# T-11_Version_1_2.net
KiCad netlist of a schematic drawn in EAGLE
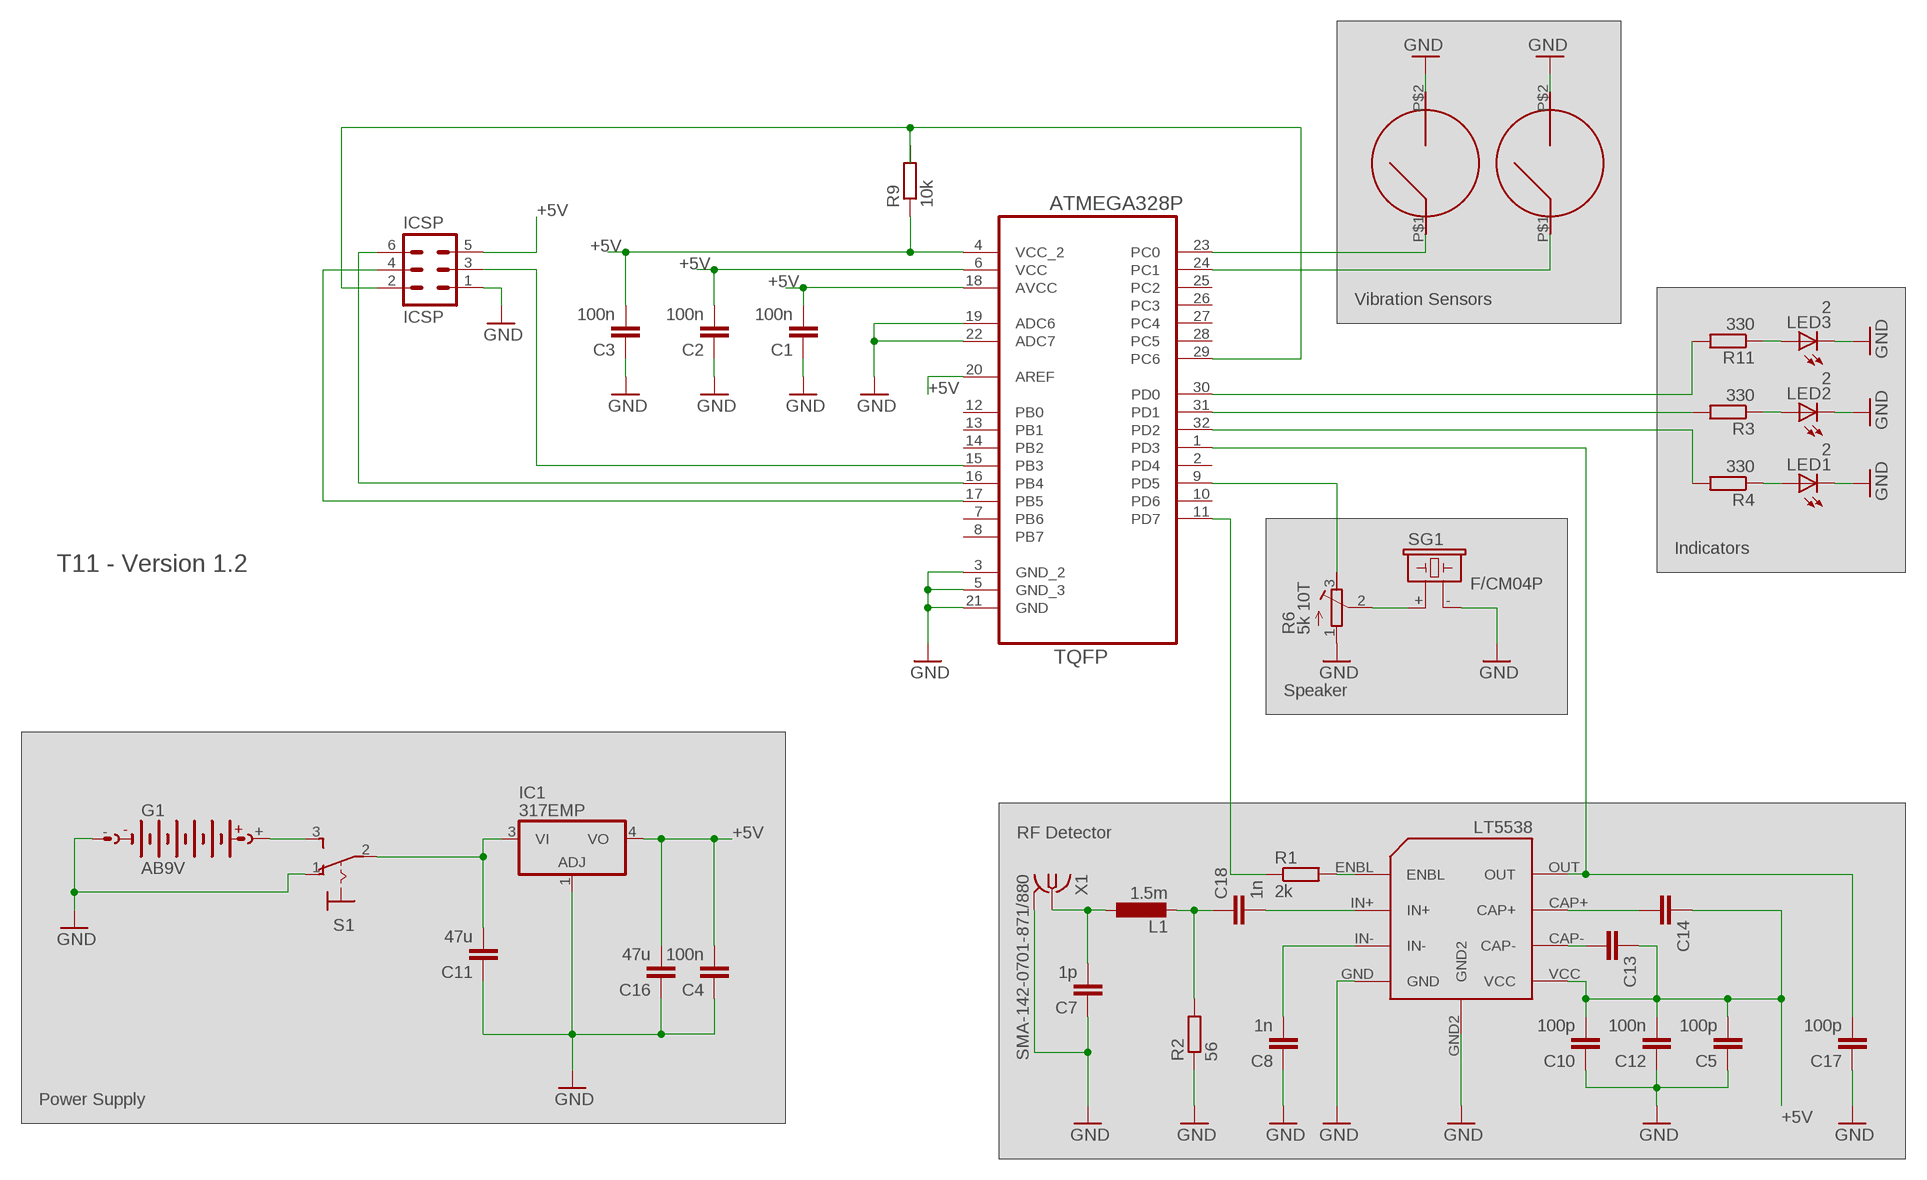
[diagram p0: schematic, sheet 1]

(export (version "E")
  (design (tool "Eeschema 10.0.6"))
  (components
    (comp (ref "C1")
      (value "100n")
      (footprint "eagle-import:C4532")
      (libsource (lib "eagle-import") (part "C-EUC4532"))
    )
    (comp (ref "C2")
      (value "100n")
      (footprint "eagle-import:C4532")
      (libsource (lib "eagle-import") (part "C-EUC4532"))
    )
    (comp (ref "C3")
      (value "100n")
      (footprint "eagle-import:C4532")
      (libsource (lib "eagle-import") (part "C-EUC4532"))
    )
    (comp (ref "C4")
      (value "100n")
      (footprint "eagle-import:C4532")
      (libsource (lib "eagle-import") (part "C-EUC4532"))
    )
    (comp (ref "C5")
      (value "100p")
      (footprint "eagle-import:C4532")
      (libsource (lib "eagle-import") (part "C-EUC4532"))
    )
    (comp (ref "C7")
      (value "1p")
      (footprint "eagle-import:C4532")
      (libsource (lib "eagle-import") (part "C-EUC4532"))
    )
    (comp (ref "C8")
      (value "1n")
      (footprint "eagle-import:C4532")
      (libsource (lib "eagle-import") (part "C-EUC4532"))
    )
    (comp (ref "C10")
      (value "100p")
      (footprint "eagle-import:C4532")
      (libsource (lib "eagle-import") (part "C-EUC4532"))
    )
    (comp (ref "C11")
      (value "47u")
      (footprint "eagle-import:C4532")
      (libsource (lib "eagle-import") (part "C-EUC4532"))
    )
    (comp (ref "C12")
      (value "100n")
      (footprint "eagle-import:C4532")
      (libsource (lib "eagle-import") (part "C-EUC4532"))
    )
    (comp (ref "C13")
      (value "C-EUC4532")
      (footprint "eagle-import:C4532")
      (libsource (lib "eagle-import") (part "C-EUC4532"))
    )
    (comp (ref "C14")
      (value "C-EUC4532")
      (footprint "eagle-import:C4532")
      (libsource (lib "eagle-import") (part "C-EUC4532"))
    )
    (comp (ref "C16")
      (value "47u")
      (footprint "eagle-import:C4532")
      (libsource (lib "eagle-import") (part "C-EUC4532"))
    )
    (comp (ref "C17")
      (value "100p")
      (footprint "eagle-import:C4532")
      (libsource (lib "eagle-import") (part "C-EUC4532"))
    )
    (comp (ref "C18")
      (value "1n")
      (footprint "eagle-import:C4532")
      (libsource (lib "eagle-import") (part "C-EUC4532"))
    )
    (comp (ref "G1")
      (value "AB9V")
      (footprint "eagle-import:AB9V")
      (libsource (lib "eagle-import") (part "AB9V"))
    )
    (comp (ref "IC1")
      (value "317EMP")
      (footprint "eagle-import:SOT223")
      (libsource (lib "eagle-import") (part "317EMP"))
    )
    (comp (ref "ICSP")
      (value "ICSP")
      (footprint "eagle-import:MA03-2")
      (libsource (lib "eagle-import") (part "MA03-2"))
    )
    (comp (ref "L1")
      (value "1.5m")
      (footprint "eagle-import:L4532P")
      (libsource (lib "eagle-import") (part "L-EUL4532P"))
    )
    (comp (ref "LED1")
      (value "2")
      (footprint "eagle-import:LED3MM")
      (libsource (lib "eagle-import") (part "LED3MM"))
    )
    (comp (ref "LED2")
      (value "2")
      (footprint "eagle-import:LED3MM")
      (libsource (lib "eagle-import") (part "LED3MM"))
    )
    (comp (ref "LED3")
      (value "2")
      (footprint "eagle-import:LED3MM")
      (libsource (lib "eagle-import") (part "LED3MM"))
    )
    (comp (ref "R1")
      (value "2k")
      (footprint "eagle-import:R3225")
      (libsource (lib "eagle-import") (part "R-EU_R3225"))
    )
    (comp (ref "R2")
      (value "56")
      (footprint "eagle-import:R3225")
      (libsource (lib "eagle-import") (part "R-EU_R3225"))
    )
    (comp (ref "R3")
      (value "330")
      (footprint "eagle-import:R3225")
      (libsource (lib "eagle-import") (part "R-EU_R3225"))
    )
    (comp (ref "R4")
      (value "330")
      (footprint "eagle-import:R3225")
      (libsource (lib "eagle-import") (part "R-EU_R3225"))
    )
    (comp (ref "R6")
      (value "5k 10T")
      (footprint "eagle-import:RTRIMTS63Y")
      (libsource (lib "eagle-import") (part "R-TRIMMTS63Y"))
    )
    (comp (ref "R9")
      (value "10k")
      (footprint "eagle-import:R3225")
      (libsource (lib "eagle-import") (part "R-EU_R3225"))
    )
    (comp (ref "R11")
      (value "330")
      (footprint "eagle-import:R3225")
      (libsource (lib "eagle-import") (part "R-EU_R3225"))
    )
    (comp (ref "S1")
      (value "320-916")
      (footprint "eagle-import:320-916")
      (libsource (lib "eagle-import") (part "320-916"))
    )
    (comp (ref "SG1")
      (value "F/CM04P")
      (footprint "eagle-import:F_CM04P")
      (libsource (lib "eagle-import") (part "F/CM04P"))
    )
    (comp (ref "U$1")
      (value "LT5538")
      (footprint "eagle-import:LT5538")
      (libsource (lib "eagle-import") (part "LT5538"))
    )
    (comp (ref "U$2")
      (value "SW-1801X")
      (footprint "eagle-import:SW-1801X")
      (libsource (lib "eagle-import") (part "SW-1801X"))
    )
    (comp (ref "U$3")
      (value "SW-1801X")
      (footprint "eagle-import:SW-1801X")
      (libsource (lib "eagle-import") (part "SW-1801X"))
    )
    (comp (ref "U1")
      (value "ATMEGA328P-AU")
      (footprint "eagle-import:QFP80P900X900X120-32N")
      (libsource (lib "eagle-import") (part "ATMEGA328P-AU"))
    )
    (comp (ref "X1")
      (value "SMA-142-0701-871/880")
      (footprint "eagle-import:SMA-142-0701-871")
      (fields (field (name "MF") "JOHNSON COMPONENTS") (field (name "MPN") "142-0701-871"))
      (libsource (lib "eagle-import") (part "SMA-142-0701-871/880"))
    )
  )
  (nets
    (net (code "1") (name "/+5V") (class "Default")
      (node (ref "C1") (pin "2") (pinfunction "2_2") (pintype "passive"))
      (node (ref "C10") (pin "2") (pinfunction "2_2") (pintype "passive"))
      (node (ref "C12") (pin "2") (pinfunction "2_2") (pintype "passive"))
      (node (ref "C13") (pin "1") (pinfunction "1_1") (pintype "passive"))
      (node (ref "C14") (pin "1") (pinfunction "1_1") (pintype "passive"))
      (node (ref "C16") (pin "2") (pinfunction "2_2") (pintype "passive"))
      (node (ref "C2") (pin "2") (pinfunction "2_2") (pintype "passive"))
      (node (ref "C3") (pin "2") (pinfunction "2_2") (pintype "passive"))
      (node (ref "C4") (pin "2") (pinfunction "2_2") (pintype "passive"))
      (node (ref "C5") (pin "2") (pinfunction "2_2") (pintype "passive"))
      (node (ref "IC1") (pin "4") (pinfunction "VO_4") (pintype "passive"))
      (node (ref "ICSP") (pin "5") (pinfunction "5_5") (pintype "passive"))
      (node (ref "R9") (pin "1") (pinfunction "1_1") (pintype "passive"))
      (node (ref "U$1") (pin "VCC") (pinfunction "VCC_VCC") (pintype "power_in"))
      (node (ref "U1") (pin "18") (pinfunction "AVCC_18") (pintype "power_in"))
      (node (ref "U1") (pin "20") (pinfunction "AREF_20") (pintype "input"))
      (node (ref "U1") (pin "4") (pinfunction "VCC_2_4") (pintype "power_in"))
      (node (ref "U1") (pin "6") (pinfunction "VCC_6") (pintype "power_in"))
    )
    (net (code "2") (name "GND") (class "Default")
      (node (ref "C1") (pin "1") (pinfunction "1_1") (pintype "passive"))
      (node (ref "C10") (pin "1") (pinfunction "1_1") (pintype "passive"))
      (node (ref "C11") (pin "1") (pinfunction "1_1") (pintype "passive"))
      (node (ref "C12") (pin "1") (pinfunction "1_1") (pintype "passive"))
      (node (ref "C16") (pin "1") (pinfunction "1_1") (pintype "passive"))
      (node (ref "C17") (pin "1") (pinfunction "1_1") (pintype "passive"))
      (node (ref "C2") (pin "1") (pinfunction "1_1") (pintype "passive"))
      (node (ref "C3") (pin "1") (pinfunction "1_1") (pintype "passive"))
      (node (ref "C4") (pin "1") (pinfunction "1_1") (pintype "passive"))
      (node (ref "C5") (pin "1") (pinfunction "1_1") (pintype "passive"))
      (node (ref "C7") (pin "1") (pinfunction "1_1") (pintype "passive"))
      (node (ref "C8") (pin "1") (pinfunction "1_1") (pintype "passive"))
      (node (ref "G1") (pin "-") (pinfunction "-_-") (pintype "passive"))
      (node (ref "IC1") (pin "1") (pinfunction "ADJ_1") (pintype "input"))
      (node (ref "ICSP") (pin "1") (pinfunction "1_1") (pintype "passive"))
      (node (ref "LED1") (pin "K") (pinfunction "C_K") (pintype "passive"))
      (node (ref "LED2") (pin "K") (pinfunction "C_K") (pintype "passive"))
      (node (ref "LED3") (pin "K") (pinfunction "C_K") (pintype "passive"))
      (node (ref "R2") (pin "1") (pinfunction "1_1") (pintype "passive"))
      (node (ref "R6") (pin "1") (pinfunction "A_1") (pintype "passive"))
      (node (ref "S1") (pin "1") (pinfunction "O_1") (pintype "passive"))
      (node (ref "SG1") (pin "-") (pinfunction "2_-") (pintype "passive"))
      (node (ref "U$1") (pin "GND") (pinfunction "GND_GND") (pintype "power_in"))
      (node (ref "U$1") (pin "GND2") (pinfunction "GND2_GND2") (pintype "bidirectional"))
      (node (ref "U$2") (pin "P$2") (pinfunction "P$2_P$2") (pintype "bidirectional"))
      (node (ref "U$3") (pin "P$2") (pinfunction "P$2_P$2") (pintype "bidirectional"))
      (node (ref "U1") (pin "19") (pinfunction "ADC6_19") (pintype "input"))
      (node (ref "U1") (pin "21") (pinfunction "GND_21") (pintype "passive"))
      (node (ref "U1") (pin "22") (pinfunction "ADC7_22") (pintype "input"))
      (node (ref "U1") (pin "3") (pinfunction "GND_2_3") (pintype "passive"))
      (node (ref "U1") (pin "5") (pinfunction "GND_3_5") (pintype "passive"))
      (node (ref "X1") (pin "2@1") (pinfunction "2_2@1") (pintype "passive"))
      (node (ref "X1") (pin "2@2") (pinfunction "2_2@2") (pintype "passive"))
      (node (ref "X1") (pin "2@3") (pinfunction "2_2@3") (pintype "passive"))
      (node (ref "X1") (pin "2@4") (pinfunction "2_2@4") (pintype "passive"))
    )
    (net (code "3") (name "Net-(C7-Pad2)") (class "Default")
      (node (ref "C7") (pin "2") (pinfunction "2_2") (pintype "passive"))
      (node (ref "L1") (pin "1") (pinfunction "1_1") (pintype "passive"))
      (node (ref "X1") (pin "1") (pinfunction "1_1") (pintype "passive"))
    )
    (net (code "4") (name "Net-(C8-Pad2)") (class "Default")
      (node (ref "C8") (pin "2") (pinfunction "2_2") (pintype "passive"))
      (node (ref "U$1") (pin "IN-") (pinfunction "IN-_IN-") (pintype "bidirectional"))
    )
    (net (code "5") (name "Net-(C13-Pad2)") (class "Default")
      (node (ref "C13") (pin "2") (pinfunction "2_2") (pintype "passive"))
      (node (ref "U$1") (pin "CAP-") (pinfunction "CAP-_CAP-") (pintype "bidirectional"))
    )
    (net (code "6") (name "Net-(C14-Pad2)") (class "Default")
      (node (ref "C14") (pin "2") (pinfunction "2_2") (pintype "passive"))
      (node (ref "U$1") (pin "CAP+") (pinfunction "CAP+_CAP+") (pintype "bidirectional"))
    )
    (net (code "7") (name "Net-(C18-Pad1)") (class "Default")
      (node (ref "C18") (pin "1") (pinfunction "1_1") (pintype "passive"))
      (node (ref "L1") (pin "2") (pinfunction "2_2") (pintype "passive"))
      (node (ref "R2") (pin "2") (pinfunction "2_2") (pintype "passive"))
    )
    (net (code "8") (name "Net-(C18-Pad2)") (class "Default")
      (node (ref "C18") (pin "2") (pinfunction "2_2") (pintype "passive"))
      (node (ref "U$1") (pin "IN+") (pinfunction "IN+_IN+") (pintype "bidirectional"))
    )
    (net (code "9") (name "Net-(IC1-VI)") (class "Default")
      (node (ref "C11") (pin "2") (pinfunction "2_2") (pintype "passive"))
      (node (ref "IC1") (pin "3") (pinfunction "VI_3") (pintype "input"))
      (node (ref "S1") (pin "2") (pinfunction "P_2") (pintype "passive"))
    )
    (net (code "10") (name "Net-(LED1-PadA)") (class "Default")
      (node (ref "LED1") (pin "A") (pinfunction "A_A") (pintype "passive"))
      (node (ref "R4") (pin "1") (pinfunction "1_1") (pintype "passive"))
    )
    (net (code "11") (name "Net-(LED2-PadA)") (class "Default")
      (node (ref "LED2") (pin "A") (pinfunction "A_A") (pintype "passive"))
      (node (ref "R3") (pin "1") (pinfunction "1_1") (pintype "passive"))
    )
    (net (code "12") (name "Net-(LED3-PadA)") (class "Default")
      (node (ref "LED3") (pin "A") (pinfunction "A_A") (pintype "passive"))
      (node (ref "R11") (pin "1") (pinfunction "1_1") (pintype "passive"))
    )
    (net (code "13") (name "Net-(R1-Pad2)") (class "Default")
      (node (ref "R1") (pin "2") (pinfunction "2_2") (pintype "passive"))
      (node (ref "U$1") (pin "ENBL") (pinfunction "ENBL_ENBL") (pintype "bidirectional"))
    )
    (net (code "14") (name "Net-(R6-E)") (class "Default")
      (node (ref "R6") (pin "3") (pinfunction "E_3") (pintype "passive"))
      (node (ref "U1") (pin "9") (pinfunction "PD5_9") (pintype "bidirectional"))
    )
    (net (code "15") (name "Net-(R6-S)") (class "Default")
      (node (ref "R6") (pin "2") (pinfunction "S_2") (pintype "passive"))
      (node (ref "SG1") (pin "+") (pinfunction "1_+") (pintype "passive"))
    )
    (net (code "16") (name "Net-(S1-S)") (class "Default")
      (node (ref "G1") (pin "+") (pinfunction "+_+") (pintype "passive"))
      (node (ref "S1") (pin "3") (pinfunction "S_3") (pintype "passive"))
    )
    (net (code "17") (name "Net-(U1-PB3)") (class "Default")
      (node (ref "ICSP") (pin "3") (pinfunction "3_3") (pintype "passive"))
      (node (ref "U1") (pin "15") (pinfunction "PB3_15") (pintype "bidirectional"))
    )
    (net (code "18") (name "Net-(U1-PB4)") (class "Default")
      (node (ref "ICSP") (pin "6") (pinfunction "6_6") (pintype "passive"))
      (node (ref "U1") (pin "16") (pinfunction "PB4_16") (pintype "bidirectional"))
    )
    (net (code "19") (name "Net-(U1-PB5)") (class "Default")
      (node (ref "ICSP") (pin "4") (pinfunction "4_4") (pintype "passive"))
      (node (ref "U1") (pin "17") (pinfunction "PB5_17") (pintype "bidirectional"))
    )
    (net (code "20") (name "Net-(U1-PC0)") (class "Default")
      (node (ref "U$3") (pin "P$1") (pinfunction "P$1_P$1") (pintype "bidirectional"))
      (node (ref "U1") (pin "23") (pinfunction "PC0_23") (pintype "bidirectional"))
    )
    (net (code "21") (name "Net-(U1-PC1)") (class "Default")
      (node (ref "U$2") (pin "P$1") (pinfunction "P$1_P$1") (pintype "bidirectional"))
      (node (ref "U1") (pin "24") (pinfunction "PC1_24") (pintype "bidirectional"))
    )
    (net (code "22") (name "Net-(U1-PC6)") (class "Default")
      (node (ref "ICSP") (pin "2") (pinfunction "2_2") (pintype "passive"))
      (node (ref "R9") (pin "2") (pinfunction "2_2") (pintype "passive"))
      (node (ref "U1") (pin "29") (pinfunction "PC6_29") (pintype "bidirectional"))
    )
    (net (code "23") (name "Net-(U1-PD0)") (class "Default")
      (node (ref "R11") (pin "2") (pinfunction "2_2") (pintype "passive"))
      (node (ref "U1") (pin "30") (pinfunction "PD0_30") (pintype "bidirectional"))
    )
    (net (code "24") (name "Net-(U1-PD1)") (class "Default")
      (node (ref "R3") (pin "2") (pinfunction "2_2") (pintype "passive"))
      (node (ref "U1") (pin "31") (pinfunction "PD1_31") (pintype "bidirectional"))
    )
    (net (code "25") (name "Net-(U1-PD2)") (class "Default")
      (node (ref "R4") (pin "2") (pinfunction "2_2") (pintype "passive"))
      (node (ref "U1") (pin "32") (pinfunction "PD2_32") (pintype "bidirectional"))
    )
    (net (code "26") (name "Net-(U1-PD3)") (class "Default")
      (node (ref "C17") (pin "2") (pinfunction "2_2") (pintype "passive"))
      (node (ref "U$1") (pin "OUT") (pinfunction "OUT_OUT") (pintype "output"))
      (node (ref "U1") (pin "1") (pinfunction "PD3_1") (pintype "bidirectional"))
    )
    (net (code "27") (name "Net-(U1-PD7)") (class "Default")
      (node (ref "R1") (pin "1") (pinfunction "1_1") (pintype "passive"))
      (node (ref "U1") (pin "11") (pinfunction "PD7_11") (pintype "bidirectional"))
    )
    (net (code "28") (name "unconnected-(U1-PB0-Pad12)") (class "Default")
      (node (ref "U1") (pin "12") (pinfunction "PB0_12") (pintype "bidirectional"))
    )
    (net (code "29") (name "unconnected-(U1-PB1-Pad13)") (class "Default")
      (node (ref "U1") (pin "13") (pinfunction "PB1_13") (pintype "bidirectional"))
    )
    (net (code "30") (name "unconnected-(U1-PB2-Pad14)") (class "Default")
      (node (ref "U1") (pin "14") (pinfunction "PB2_14") (pintype "bidirectional"))
    )
    (net (code "31") (name "unconnected-(U1-PB6-Pad7)") (class "Default")
      (node (ref "U1") (pin "7") (pinfunction "PB6_7") (pintype "bidirectional"))
    )
    (net (code "32") (name "unconnected-(U1-PB7-Pad8)") (class "Default")
      (node (ref "U1") (pin "8") (pinfunction "PB7_8") (pintype "bidirectional"))
    )
    (net (code "33") (name "unconnected-(U1-PC2-Pad25)") (class "Default")
      (node (ref "U1") (pin "25") (pinfunction "PC2_25") (pintype "bidirectional"))
    )
    (net (code "34") (name "unconnected-(U1-PC3-Pad26)") (class "Default")
      (node (ref "U1") (pin "26") (pinfunction "PC3_26") (pintype "bidirectional"))
    )
    (net (code "35") (name "unconnected-(U1-PC4-Pad27)") (class "Default")
      (node (ref "U1") (pin "27") (pinfunction "PC4_27") (pintype "bidirectional"))
    )
    (net (code "36") (name "unconnected-(U1-PC5-Pad28)") (class "Default")
      (node (ref "U1") (pin "28") (pinfunction "PC5_28") (pintype "bidirectional"))
    )
    (net (code "37") (name "unconnected-(U1-PD4-Pad2)") (class "Default")
      (node (ref "U1") (pin "2") (pinfunction "PD4_2") (pintype "bidirectional"))
    )
    (net (code "38") (name "unconnected-(U1-PD6-Pad10)") (class "Default")
      (node (ref "U1") (pin "10") (pinfunction "PD6_10") (pintype "bidirectional"))
    )
  )
)
